# SCH.net
KiCad netlist of a schematic drawn in EasyEDA
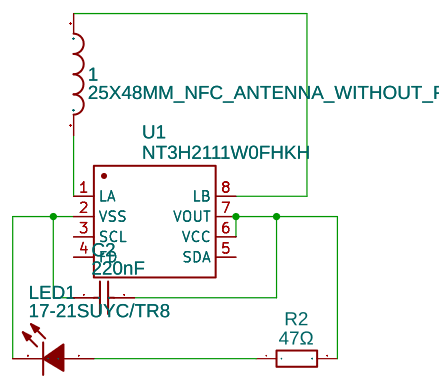
[diagram p0: schematic sheet]

(export (version "E")
  (design (tool "Eeschema 10.0.6"))
  (components
    (comp (ref "1")
      (value "25X48MM_NFC_ANTENNA_WITHOUT_PADS")
      (libsource (lib "") (part "25X48MM_NFC_ANTENNA_WITHOUT_PADS"))
    )
    (comp (ref "C2")
      (value "220nF")
      (fields
        (field (name "Manufacturer Part") "CL10B224KA8NNNC")
        (field (name "Manufacturer") "SAMSUNG(三星)")
      )
      (libsource (lib "") (part "CL10B224KA8NNNC"))
    )
    (comp (ref "LED1")
      (value "17-21SUYC/TR8")
      (fields (field (name "Manufacturer Part") "KT-0805黄灯") (field (name "Manufacturer") "KENTO"))
      (libsource (lib "") (part "17-21SUYC/TR8"))
    )
    (comp (ref "R2")
      (value "47Ω")
      (fields
        (field (name "Manufacturer Part") "0603WAF470JT5E")
        (field (name "Manufacturer") "UNI-ROYAL(厚声)")
      )
      (libsource (lib "") (part "0603WAF470JT5E"))
    )
    (comp (ref "U1")
      (value "NT3H2111W0FHKH")
      (fields (field (name "Manufacturer") "NXP(恩智浦)"))
      (libsource (lib "") (part "NT3H2111W0FHKH"))
    )
  )
  (nets
    (net (code "1") (name "Net-(LED1-+)") (class "Default")
      (node (ref "LED1") (pin "1") (pinfunction "+_1") (pintype "unspecified"))
      (node (ref "R2") (pin "1") (pinfunction "1_1") (pintype "input"))
    )
    (net (code "2") (name "Net-(LED1--)") (class "Default")
      (node (ref "C2") (pin "1") (pinfunction "1_1") (pintype "input"))
      (node (ref "LED1") (pin "2") (pinfunction "-_2") (pintype "unspecified"))
      (node (ref "U1") (pin "2") (pinfunction "VSS_2") (pintype "unspecified"))
    )
    (net (code "3") (name "Net-(U1-LA)") (class "Default")
      (node (ref "1") (pin "P$2") (pinfunction "P$2_P$2") (pintype "bidirectional"))
      (node (ref "U1") (pin "1") (pinfunction "LA_1") (pintype "unspecified"))
    )
    (net (code "4") (name "Net-(U1-LB)") (class "Default")
      (node (ref "1") (pin "P$1") (pinfunction "P$1_P$1") (pintype "bidirectional"))
      (node (ref "U1") (pin "8") (pinfunction "LB_8") (pintype "unspecified"))
    )
    (net (code "5") (name "Net-(U1-VCC)") (class "Default")
      (node (ref "C2") (pin "2") (pinfunction "2_2") (pintype "input"))
      (node (ref "R2") (pin "2") (pinfunction "2_2") (pintype "input"))
      (node (ref "U1") (pin "6") (pinfunction "VCC_6") (pintype "unspecified"))
      (node (ref "U1") (pin "7") (pinfunction "VOUT_7") (pintype "unspecified"))
    )
    (net (code "6") (name "unconnected-(U1-FD-Pad4)") (class "Default")
      (node (ref "U1") (pin "4") (pinfunction "FD_4") (pintype "unspecified"))
    )
    (net (code "7") (name "unconnected-(U1-SCL-Pad3)") (class "Default")
      (node (ref "U1") (pin "3") (pinfunction "SCL_3") (pintype "unspecified"))
    )
    (net (code "8") (name "unconnected-(U1-SDA-Pad5)") (class "Default")
      (node (ref "U1") (pin "5") (pinfunction "SDA_5") (pintype "unspecified"))
    )
  )
)
